# PUE.net
KiCad netlist of a schematic drawn in Altium Designer
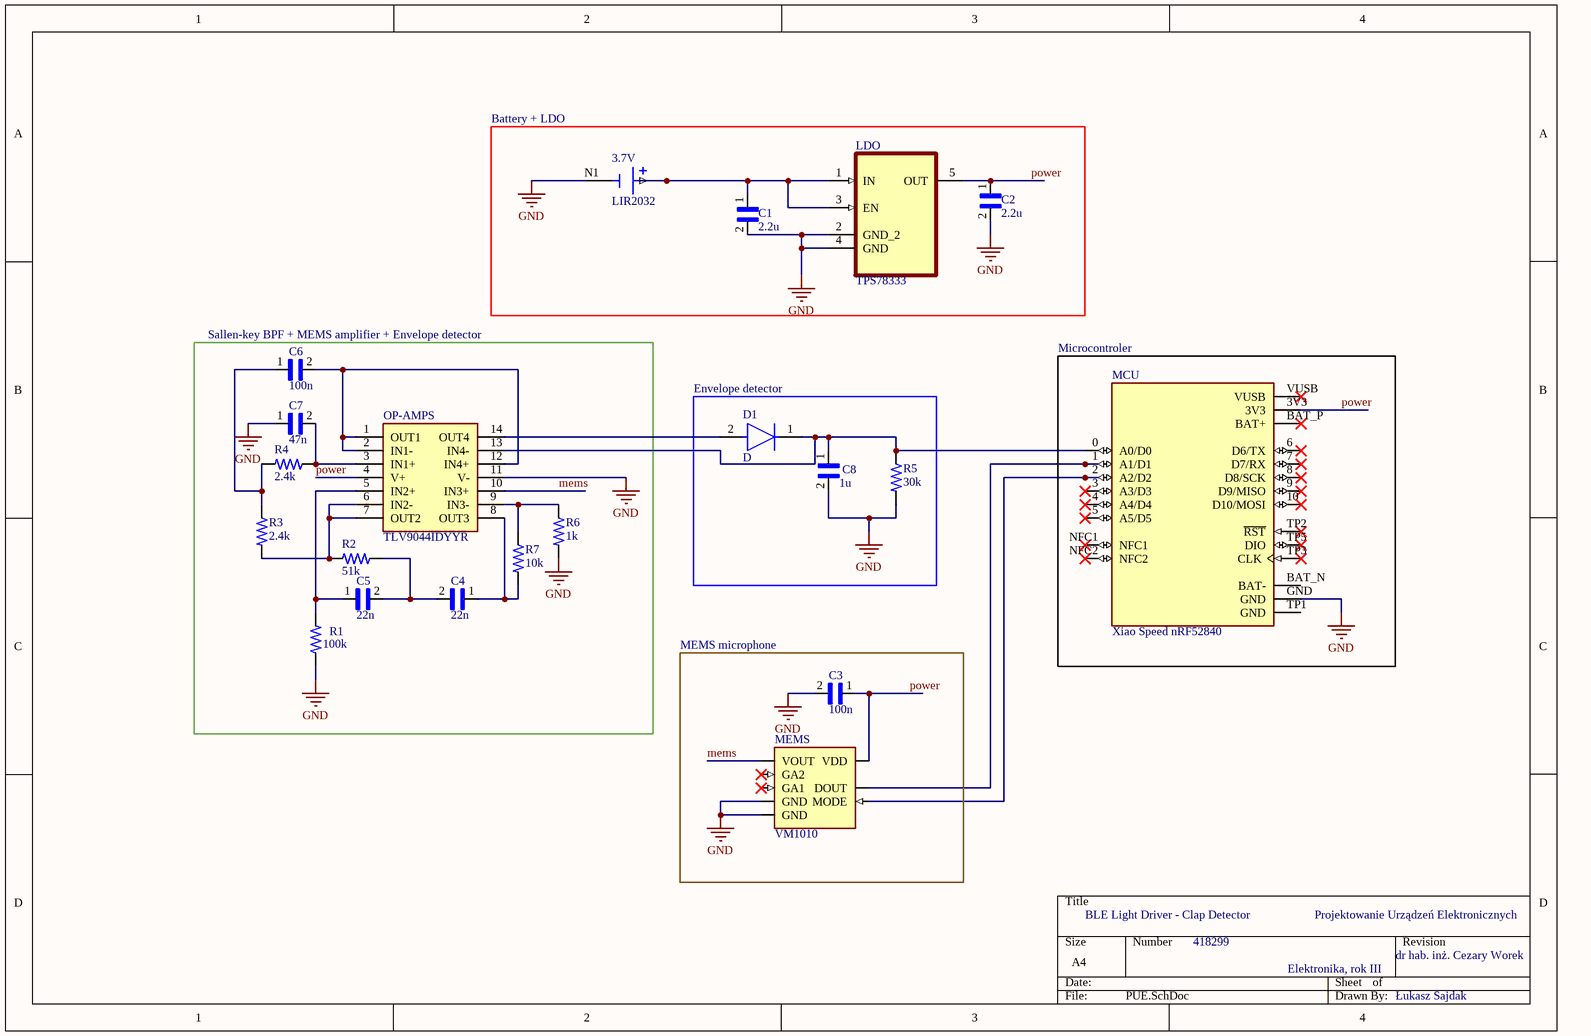
[diagram p0: PUE.SchDoc]

(export (version "E")
  (design (tool "Eeschema 10.0.6"))
  (components
    (comp (ref "3.7V")
      (value "LIR2032")
      (footprint "BAT_BAT-HLD-001")
      (description "Holder for CR2032 and CR2025 Batteries, Surface-Mount, Bulk Packaging")
      (fields (field (name "MF") "Linx Technologies") (field (name "MP") "BAT-HLD-001"))
      (libsource (lib "BAT-HLD-001") (part "BAT-HLD-001"))
    )
    (comp (ref "C1")
      (value "2.2u")
      (footprint "CAPC2012X135N")
      (description "CAP CER 2.2UF 35V X6S 0805")
      (fields (field (name "MP") "GRT21BC8YA225KE13L"))
      (libsource (lib "GRT21BC8YA225KE13L") (part "GRT21BC8YA225KE13L"))
    )
    (comp (ref "C2")
      (value "2.2u")
      (footprint "CAPC2012X135N")
      (description "CAP CER 2.2UF 35V X6S 0805")
      (fields (field (name "MP") "GRT21BC8YA225KE13L"))
      (libsource (lib "GRT21BC8YA225KE13L") (part "GRT21BC8YA225KE13L"))
    )
    (comp (ref "C3")
      (value "100n")
      (footprint "CAPC2012X135N")
      (description "CAP CER 2.2UF 35V X6S 0805")
      (fields (field (name "MP") "GRT21BC8YA225KE13L"))
      (libsource (lib "") (part "GRT21BC8YA225KE13L_2"))
    )
    (comp (ref "C4")
      (value "22n")
      (footprint "CAPC2012X135N")
      (description "CAP CER 2.2UF 35V X6S 0805")
      (fields (field (name "MP") "GRT21BC8YA225KE13L"))
      (libsource (lib "") (part "GRT21BC8YA225KE13L_2"))
    )
    (comp (ref "C5")
      (value "22n")
      (footprint "CAPC2012X135N")
      (description "CAP CER 2.2UF 35V X6S 0805")
      (fields (field (name "MP") "GRT21BC8YA225KE13L"))
      (libsource (lib "") (part "GRT21BC8YA225KE13L_1"))
    )
    (comp (ref "C6")
      (value "100n")
      (footprint "CAPC2012X135N")
      (description "CAP CER 2.2UF 35V X6S 0805")
      (fields (field (name "MP") "GRT21BC8YA225KE13L"))
      (libsource (lib "") (part "GRT21BC8YA225KE13L_1"))
    )
    (comp (ref "C7")
      (value "47n")
      (footprint "CAPC2012X135N")
      (description "CAP CER 2.2UF 35V X6S 0805")
      (fields (field (name "MP") "GRT21BC8YA225KE13L"))
      (libsource (lib "") (part "GRT21BC8YA225KE13L_1"))
    )
    (comp (ref "C8")
      (value "1u")
      (footprint "CAPC2012X135N")
      (description "CAP CER 2.2UF 35V X6S 0805")
      (fields (field (name "MP") "GRT21BC8YA225KE13L"))
      (libsource (lib "GRT21BC8YA225KE13L") (part "GRT21BC8YA225KE13L"))
    )
    (comp (ref "D1")
      (value "D")
      (footprint "FP-017AG-MFG")
      (description "DIODE GEN PURP 100V 200MA DO35")
      (fields (field (name "VOLTAGE") "100V"))
      (libsource (lib "Altium Content Vault") (part "d7152d700b627762746794eb795d46e"))
    )
    (comp (ref "LDO")
      (value "TPS78333")
      (footprint "SOT95P280X110-5N")
      (description "150-mA, nano-IQ, low-dropout voltage regulator with enable from -40Â°C to +105Â°C")
      (fields (field (name "MF") "Texas Instruments") (field (name "MP") "TPS78326DDCT"))
      (libsource (lib "TPS78326DDCT") (part "TPS78326DDCT"))
    )
    (comp (ref "MCU")
      (value "Xiao Speed nRF52840")
      (footprint "MODULE_102010448")
      (description "- nRF52840 Transceiver; Bluetooth® 5.x Evaluation Board")
      (fields (field (name "MF") "Seeed Technology Co., Ltd") (field (name "MP") "102010448"))
      (libsource (lib "102010448") (part "102010448"))
    )
    (comp (ref "MEMS")
      (value "VM1010")
      (footprint "VM1010")
      (description "100 Hz ~ 10 kHz Analog Microphone Piezo MEMS Omnidirectional (-38dB Â±3dB @ 94dB SPL) Solder Pads")
      (fields (field (name "MF") "Vesper"))
      (libsource (lib "VM1010 (1)") (part "VM1010"))
    )
    (comp (ref "OP-AMPS")
      (value "TLV9044IDYYR")
      (footprint "RESC2012X65N:SOP50P326X110-14N")
      (description "Integrated Circuit")
      (fields (field (name "MOUSER PART NUMBER") "595-TLV9044IDYYR"))
      (libsource (lib "*") (part "TLV9044IDYYR"))
    )
    (comp (ref "R1")
      (value "100k")
      (footprint "RESC2012X65N")
      (description "RP 2A 0.25W 100K 0.1% 25PPM 1K RL")
      (fields (field (name "MP") "RP73PF2A100KBTDF"))
      (libsource (lib "RP73PF2A100KBTDF") (part "RP73PF2A100KBTDF"))
    )
    (comp (ref "R2")
      (value "51k")
      (footprint "RESC2012X65N")
      (description "RP 2A 0.25W 100K 0.1% 25PPM 1K RL")
      (fields (field (name "MP") "RP73PF2A100KBTDF"))
      (libsource (lib "RP73PF2A100KBTDF") (part "RP73PF2A100KBTDF"))
    )
    (comp (ref "R3")
      (value "2.4k")
      (footprint "RESC2012X65N")
      (description "RP 2A 0.25W 100K 0.1% 25PPM 1K RL")
      (fields (field (name "MP") "RP73PF2A100KBTDF"))
      (libsource (lib "RP73PF2A100KBTDF") (part "RP73PF2A100KBTDF"))
    )
    (comp (ref "R4")
      (value "2.4k")
      (footprint "RESC2012X65N")
      (description "RP 2A 0.25W 100K 0.1% 25PPM 1K RL")
      (fields (field (name "MP") "RP73PF2A100KBTDF"))
      (libsource (lib "RP73PF2A100KBTDF") (part "RP73PF2A100KBTDF"))
    )
    (comp (ref "R5")
      (value "30k")
      (footprint "RESC2012X65N")
      (description "RP 2A 0.25W 100K 0.1% 25PPM 1K RL")
      (fields (field (name "MP") "RP73PF2A100KBTDF"))
      (libsource (lib "RP73PF2A100KBTDF") (part "RP73PF2A100KBTDF"))
    )
    (comp (ref "R6")
      (value "1k")
      (footprint "RESC2012X65N")
      (description "RP 2A 0.25W 100K 0.1% 25PPM 1K RL")
      (fields (field (name "MP") "RP73PF2A100KBTDF"))
      (libsource (lib "RP73PF2A100KBTDF") (part "RP73PF2A100KBTDF"))
    )
    (comp (ref "R7")
      (value "10k")
      (footprint "RESC2012X65N")
      (description "RP 2A 0.25W 100K 0.1% 25PPM 1K RL")
      (fields (field (name "MP") "RP73PF2A100KBTDF"))
      (libsource (lib "RP73PF2A100KBTDF") (part "RP73PF2A100KBTDF"))
    )
  )
  (nets
    (net (code "1") (name "/mems") (class "Default")
      (node (ref "MEMS") (pin "1") (pinfunction "VOUT_1") (pintype "passive"))
      (node (ref "OP-AMPS") (pin "10") (pinfunction "IN3+_10") (pintype "passive"))
    )
    (net (code "2") (name "/power") (class "Default")
      (node (ref "C2") (pin "1") (pinfunction "1_1") (pintype "passive"))
      (node (ref "C3") (pin "1") (pinfunction "1_1") (pintype "passive"))
      (node (ref "LDO") (pin "5") (pinfunction "OUT_5") (pintype "passive"))
      (node (ref "MCU") (pin "3V3") (pinfunction "3V3_3V3") (pintype "passive"))
      (node (ref "MEMS") (pin "6") (pinfunction "VDD_6") (pintype "passive"))
      (node (ref "OP-AMPS") (pin "4") (pinfunction "V+_4") (pintype "passive"))
    )
    (net (code "3") (name "GND") (class "Default")
      (node (ref "3.7V") (pin "N1") (pinfunction "NEG_N1") (pintype "passive"))
      (node (ref "C1") (pin "2") (pinfunction "2_2") (pintype "passive"))
      (node (ref "C2") (pin "2") (pinfunction "2_2") (pintype "passive"))
      (node (ref "C3") (pin "2") (pinfunction "2_2") (pintype "passive"))
      (node (ref "C7") (pin "1") (pinfunction "1_1") (pintype "passive"))
      (node (ref "C8") (pin "2") (pinfunction "2_2") (pintype "passive"))
      (node (ref "LDO") (pin "2") (pinfunction "GND_2_2") (pintype "passive"))
      (node (ref "LDO") (pin "4") (pinfunction "GND_4") (pintype "passive"))
      (node (ref "MCU") (pin "GND") (pinfunction "GND_GND") (pintype "power_in"))
      (node (ref "MEMS") (pin "4") (pinfunction "GND_4") (pintype "power_in"))
      (node (ref "MEMS") (pin "8") (pinfunction "GND_8") (pintype "power_in"))
      (node (ref "OP-AMPS") (pin "11") (pinfunction "V-_11") (pintype "passive"))
      (node (ref "R1") (pin "1") (pinfunction "1_1") (pintype "passive"))
      (node (ref "R5") (pin "2") (pinfunction "2_2") (pintype "passive"))
      (node (ref "R6") (pin "2") (pinfunction "2_2") (pintype "passive"))
    )
    (net (code "4") (name "Net-(C4-Pad2)") (class "Default")
      (node (ref "C4") (pin "2") (pinfunction "2_2") (pintype "passive"))
      (node (ref "C5") (pin "2") (pinfunction "2_2") (pintype "passive"))
      (node (ref "R2") (pin "1") (pinfunction "1_1") (pintype "passive"))
    )
    (net (code "5") (name "Net-(C6-Pad1)") (class "Default")
      (node (ref "C6") (pin "1") (pinfunction "1_1") (pintype "passive"))
      (node (ref "R3") (pin "1") (pinfunction "1_1") (pintype "passive"))
      (node (ref "R4") (pin "2") (pinfunction "2_2") (pintype "passive"))
    )
    (net (code "6") (name "Net-(D1-A)") (class "Default")
      (node (ref "D1") (pin "2") (pinfunction "A_2") (pintype "passive"))
      (node (ref "OP-AMPS") (pin "14") (pinfunction "OUT4_14") (pintype "passive"))
    )
    (net (code "7") (name "Net-(D1-C)") (class "Default")
      (node (ref "C8") (pin "1") (pinfunction "1_1") (pintype "passive"))
      (node (ref "D1") (pin "1") (pinfunction "C_1") (pintype "passive"))
      (node (ref "MCU") (pin "0") (pinfunction "A0/D0_0") (pintype "bidirectional"))
      (node (ref "OP-AMPS") (pin "13") (pinfunction "IN4-_13") (pintype "passive"))
      (node (ref "R5") (pin "1") (pinfunction "1_1") (pintype "passive"))
    )
    (net (code "8") (name "Net-(LDO-EN)") (class "Default")
      (node (ref "3.7V") (pin "P1") (pinfunction "POS_P1") (pintype "output"))
      (node (ref "3.7V") (pin "P2") (pinfunction "POS_P2") (pintype "passive"))
      (node (ref "C1") (pin "1") (pinfunction "1_1") (pintype "passive"))
      (node (ref "LDO") (pin "1") (pinfunction "IN_1") (pintype "input"))
      (node (ref "LDO") (pin "3") (pinfunction "EN_3") (pintype "input"))
    )
    (net (code "9") (name "Net-(MCU-A1{slash}D1)") (class "Default")
      (node (ref "MCU") (pin "1") (pinfunction "A1/D1_1") (pintype "bidirectional"))
      (node (ref "MEMS") (pin "7") (pinfunction "DOUT_7") (pintype "passive"))
    )
    (net (code "10") (name "Net-(MCU-A2{slash}D2)") (class "Default")
      (node (ref "MCU") (pin "2") (pinfunction "A2/D2_2") (pintype "bidirectional"))
      (node (ref "MEMS") (pin "5") (pinfunction "MODE_5") (pintype "input"))
    )
    (net (code "11") (name "Net-(OP-AMPS-IN1+)") (class "Default")
      (node (ref "C7") (pin "2") (pinfunction "2_2") (pintype "passive"))
      (node (ref "OP-AMPS") (pin "3") (pinfunction "IN1+_3") (pintype "passive"))
      (node (ref "R4") (pin "1") (pinfunction "1_1") (pintype "passive"))
    )
    (net (code "12") (name "Net-(OP-AMPS-IN1-)") (class "Default")
      (node (ref "C6") (pin "2") (pinfunction "2_2") (pintype "passive"))
      (node (ref "OP-AMPS") (pin "1") (pinfunction "OUT1_1") (pintype "passive"))
      (node (ref "OP-AMPS") (pin "12") (pinfunction "IN4+_12") (pintype "passive"))
      (node (ref "OP-AMPS") (pin "2") (pinfunction "IN1-_2") (pintype "passive"))
    )
    (net (code "13") (name "Net-(OP-AMPS-IN2+)") (class "Default")
      (node (ref "C5") (pin "1") (pinfunction "1_1") (pintype "passive"))
      (node (ref "OP-AMPS") (pin "5") (pinfunction "IN2+_5") (pintype "passive"))
      (node (ref "R1") (pin "2") (pinfunction "2_2") (pintype "passive"))
    )
    (net (code "14") (name "Net-(OP-AMPS-IN2-)") (class "Default")
      (node (ref "OP-AMPS") (pin "6") (pinfunction "IN2-_6") (pintype "passive"))
      (node (ref "OP-AMPS") (pin "7") (pinfunction "OUT2_7") (pintype "passive"))
      (node (ref "R2") (pin "2") (pinfunction "2_2") (pintype "passive"))
      (node (ref "R3") (pin "2") (pinfunction "2_2") (pintype "passive"))
    )
    (net (code "15") (name "Net-(OP-AMPS-IN3-)") (class "Default")
      (node (ref "OP-AMPS") (pin "9") (pinfunction "IN3-_9") (pintype "passive"))
      (node (ref "R6") (pin "1") (pinfunction "1_1") (pintype "passive"))
      (node (ref "R7") (pin "1") (pinfunction "1_1") (pintype "passive"))
    )
    (net (code "16") (name "Net-(OP-AMPS-OUT3)") (class "Default")
      (node (ref "C4") (pin "1") (pinfunction "1_1") (pintype "passive"))
      (node (ref "OP-AMPS") (pin "8") (pinfunction "OUT3_8") (pintype "passive"))
      (node (ref "R7") (pin "2") (pinfunction "2_2") (pintype "passive"))
    )
    (net (code "17") (name "unconnected-(MCU-A3{slash}D3-Pad3)") (class "Default")
      (node (ref "MCU") (pin "3") (pinfunction "A3/D3_3") (pintype "bidirectional+no_connect"))
    )
    (net (code "18") (name "unconnected-(MCU-A4{slash}D4-Pad4)") (class "Default")
      (node (ref "MCU") (pin "4") (pinfunction "A4/D4_4") (pintype "bidirectional+no_connect"))
    )
    (net (code "19") (name "unconnected-(MCU-A5{slash}D5-Pad5)") (class "Default")
      (node (ref "MCU") (pin "5") (pinfunction "A5/D5_5") (pintype "bidirectional+no_connect"))
    )
    (net (code "20") (name "unconnected-(MCU-BAT+-PadBAT_P)") (class "Default")
      (node (ref "MCU") (pin "BAT_P") (pinfunction "BAT+_BAT_P") (pintype "power_in+no_connect"))
    )
    (net (code "21") (name "unconnected-(MCU-BAT--PadBAT_N)") (class "Default")
      (node (ref "MCU") (pin "BAT_N") (pinfunction "BAT-_BAT_N") (pintype "power_in"))
    )
    (net (code "22") (name "unconnected-(MCU-CLK-PadTP3)") (class "Default")
      (node (ref "MCU") (pin "TP3") (pinfunction "CLK_TP3") (pintype "input+no_connect"))
    )
    (net (code "23") (name "unconnected-(MCU-D6{slash}TX-Pad6)") (class "Default")
      (node (ref "MCU") (pin "6") (pinfunction "D6/TX_6") (pintype "bidirectional+no_connect"))
    )
    (net (code "24") (name "unconnected-(MCU-D7{slash}RX-Pad7)") (class "Default")
      (node (ref "MCU") (pin "7") (pinfunction "D7/RX_7") (pintype "bidirectional+no_connect"))
    )
    (net (code "25") (name "unconnected-(MCU-D8{slash}SCK-Pad8)") (class "Default")
      (node (ref "MCU") (pin "8") (pinfunction "D8/SCK_8") (pintype "bidirectional+no_connect"))
    )
    (net (code "26") (name "unconnected-(MCU-D9{slash}MISO-Pad9)") (class "Default")
      (node (ref "MCU") (pin "9") (pinfunction "D9/MISO_9") (pintype "bidirectional+no_connect"))
    )
    (net (code "27") (name "unconnected-(MCU-D10{slash}MOSI-Pad10)") (class "Default")
      (node (ref "MCU") (pin "10") (pinfunction "D10/MOSI_10") (pintype "bidirectional+no_connect"))
    )
    (net (code "28") (name "unconnected-(MCU-DIO-PadTP5)") (class "Default")
      (node (ref "MCU") (pin "TP5") (pinfunction "DIO_TP5") (pintype "bidirectional+no_connect"))
    )
    (net (code "29") (name "unconnected-(MCU-GND-PadTP1)") (class "Default")
      (node (ref "MCU") (pin "TP1") (pinfunction "GND_TP1") (pintype "power_in"))
    )
    (net (code "30") (name "unconnected-(MCU-PadNFC1)") (class "Default")
      (node (ref "MCU") (pin "NFC1") (pinfunction "NFC1_NFC1") (pintype "bidirectional+no_connect"))
    )
    (net (code "31") (name "unconnected-(MCU-PadNFC2)") (class "Default")
      (node (ref "MCU") (pin "NFC2") (pinfunction "NFC2_NFC2") (pintype "bidirectional+no_connect"))
    )
    (net (code "32") (name "unconnected-(MCU-PadVUSB)") (class "Default")
      (node (ref "MCU") (pin "VUSB") (pinfunction "VUSB_VUSB") (pintype "power_in+no_connect"))
    )
    (net (code "33") (name "unconnected-(MCU-~{RST}-PadTP2)") (class "Default")
      (node (ref "MCU") (pin "TP2") (pinfunction "~{RST}_TP2") (pintype "input+no_connect"))
    )
    (net (code "34") (name "unconnected-(MEMS-GA1-Pad3)") (class "Default")
      (node (ref "MEMS") (pin "3") (pinfunction "GA1_3") (pintype "input+no_connect"))
    )
    (net (code "35") (name "unconnected-(MEMS-GA2-Pad2)") (class "Default")
      (node (ref "MEMS") (pin "2") (pinfunction "GA2_2") (pintype "input+no_connect"))
    )
  )
)
